# DC_STEP_DRIVER.net
KiCad netlist of a schematic drawn in EAGLE
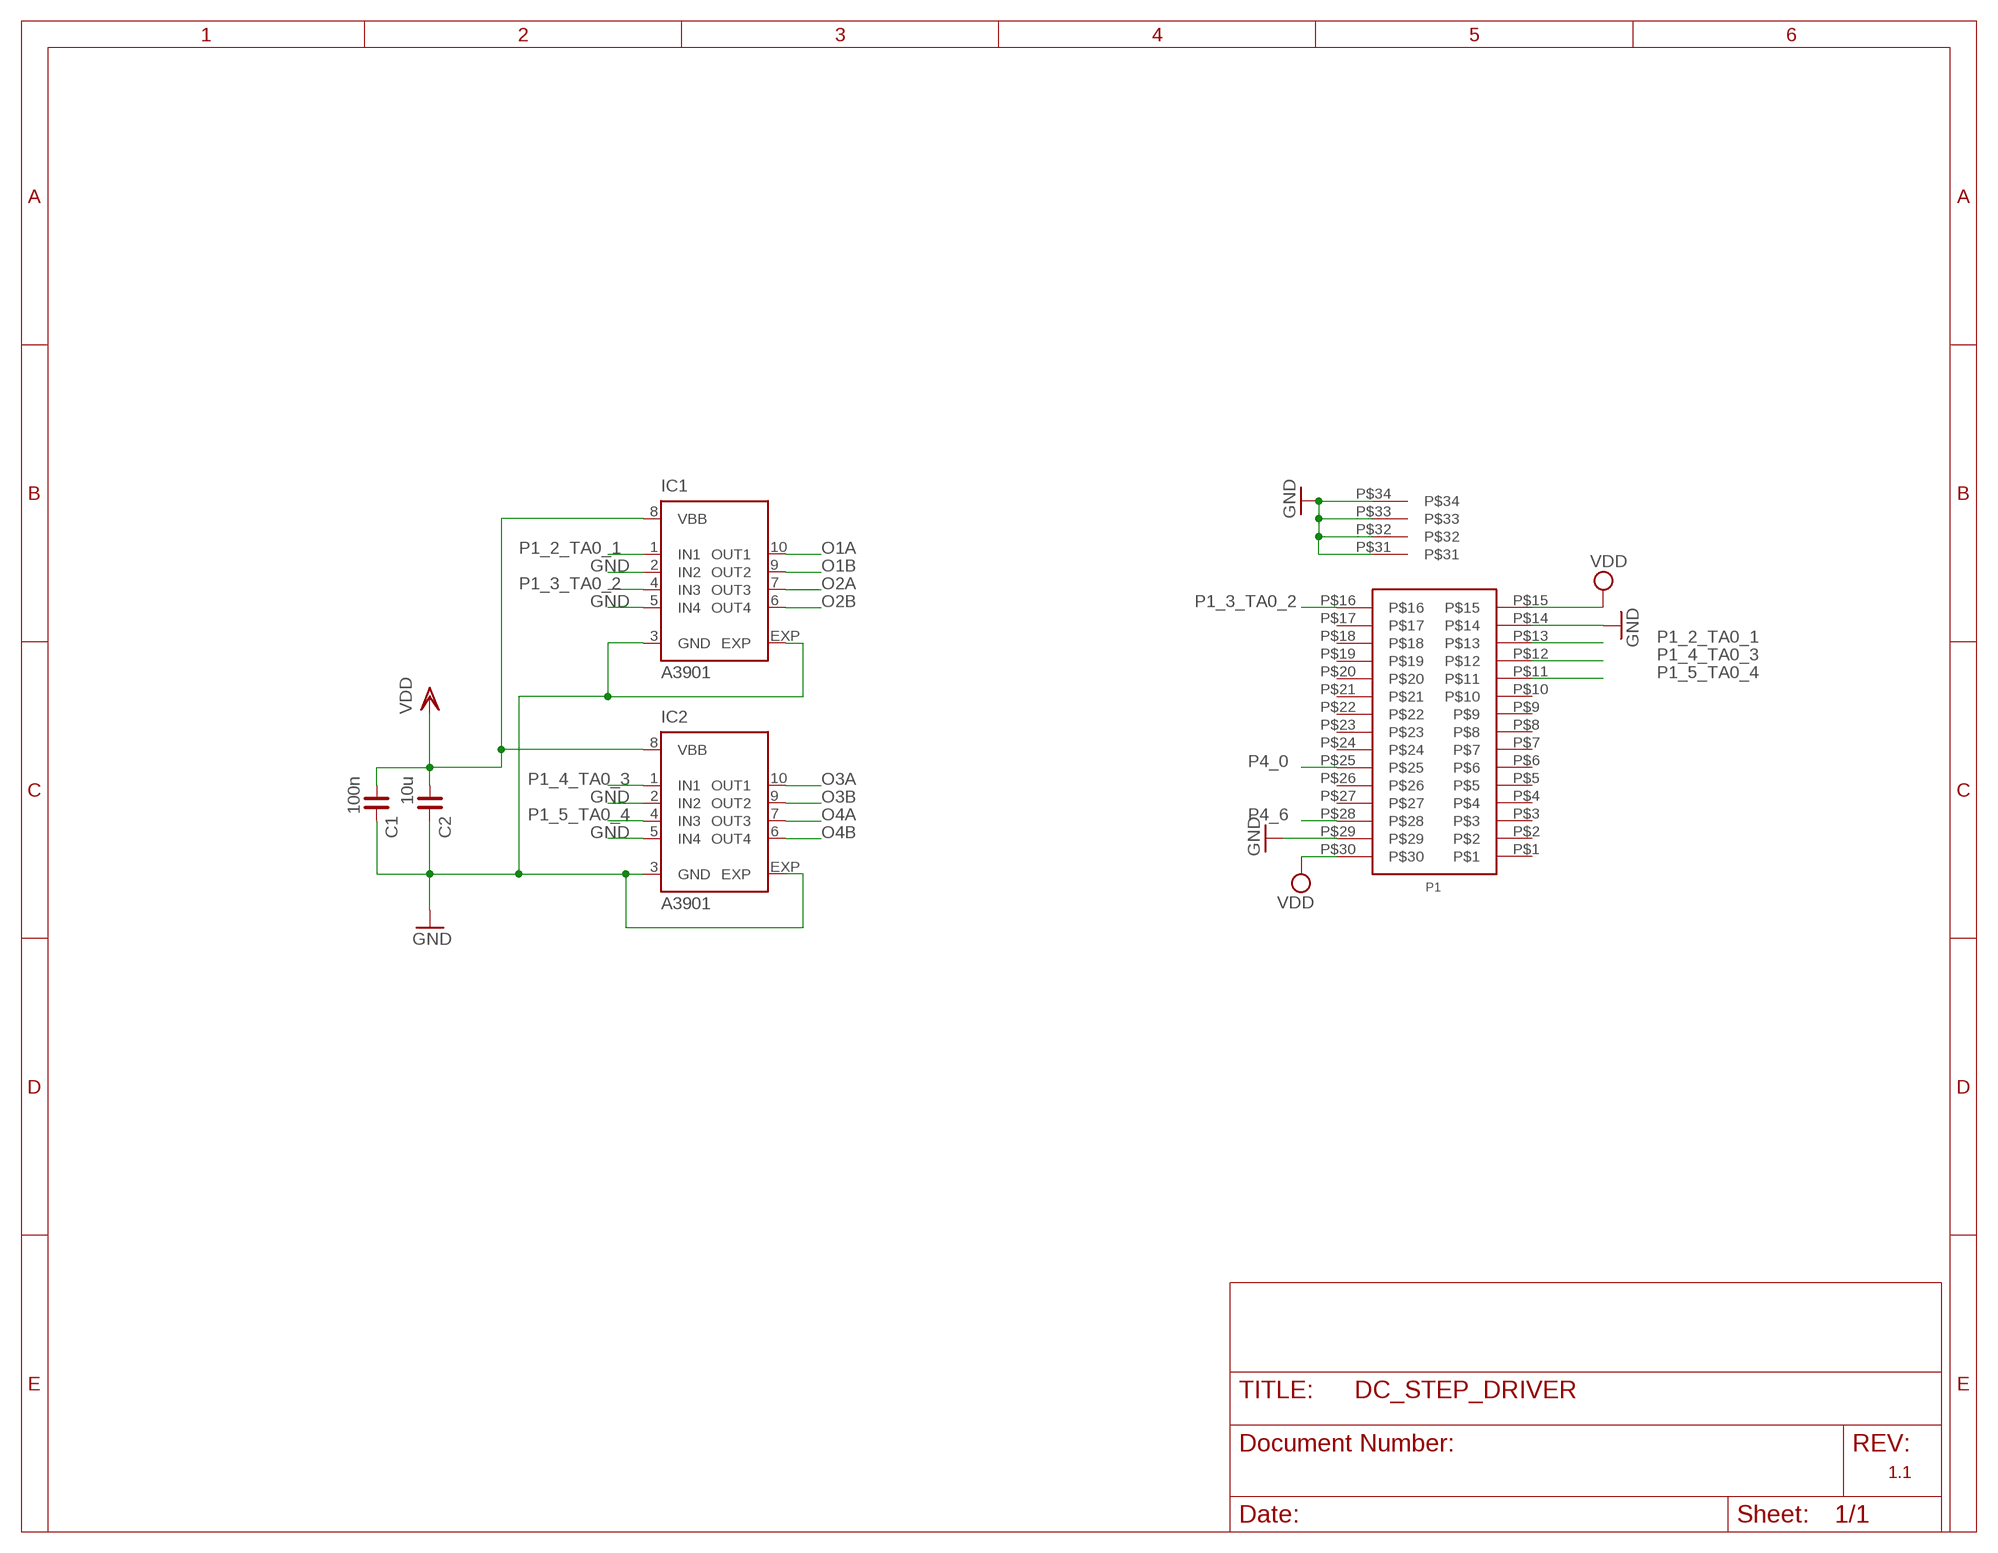
[diagram p0: schematic, sheet 1]

(export (version "E")
  (design (tool "Eeschema 10.0.6"))
  (components
    (comp (ref "C1")
      (value "100n")
      (footprint "eagle-import:C0402")
      (libsource (lib "eagle-import") (part "C_0402"))
    )
    (comp (ref "C2")
      (value "10u")
      (footprint "eagle-import:C0402")
      (libsource (lib "eagle-import") (part "C_0402"))
    )
    (comp (ref "IC1")
      (value "A3901")
      (footprint "eagle-import:DFN10-3X3")
      (fields (field (name "MPN") "A3901SEJTR-T"))
      (libsource (lib "eagle-import") (part "A3901"))
    )
    (comp (ref "IC2")
      (value "A3901")
      (footprint "eagle-import:DFN10-3X3")
      (fields (field (name "MPN") "A3901SEJTR-T"))
      (libsource (lib "eagle-import") (part "A3901"))
    )
    (comp (ref "P1")
      (value "55909-0374")
      (footprint "eagle-import:55909-0374_PLUG")
      (libsource (lib "eagle-import") (part "55909-0374_PLUG"))
    )
  )
  (nets
    (net (code "1") (name "/O1A") (class "Default")
      (node (ref "IC1") (pin "10") (pinfunction "OUT1_10") (pintype "output"))
    )
    (net (code "2") (name "/O1B") (class "Default")
      (node (ref "IC1") (pin "9") (pinfunction "OUT2_9") (pintype "output"))
    )
    (net (code "3") (name "/O2A") (class "Default")
      (node (ref "IC1") (pin "7") (pinfunction "OUT3_7") (pintype "output"))
    )
    (net (code "4") (name "/O2B") (class "Default")
      (node (ref "IC1") (pin "6") (pinfunction "OUT4_6") (pintype "output"))
    )
    (net (code "5") (name "/O3A") (class "Default")
      (node (ref "IC2") (pin "10") (pinfunction "OUT1_10") (pintype "output"))
    )
    (net (code "6") (name "/O3B") (class "Default")
      (node (ref "IC2") (pin "9") (pinfunction "OUT2_9") (pintype "output"))
    )
    (net (code "7") (name "/O4A") (class "Default")
      (node (ref "IC2") (pin "7") (pinfunction "OUT3_7") (pintype "output"))
    )
    (net (code "8") (name "/O4B") (class "Default")
      (node (ref "IC2") (pin "6") (pinfunction "OUT4_6") (pintype "output"))
    )
    (net (code "9") (name "/P1_2_TA0_1") (class "Default")
      (node (ref "IC1") (pin "1") (pinfunction "IN1_1") (pintype "input"))
      (node (ref "P1") (pin "P$13") (pinfunction "P$13_P$13") (pintype "bidirectional"))
    )
    (net (code "10") (name "/P1_3_TA0_2") (class "Default")
      (node (ref "IC1") (pin "4") (pinfunction "IN3_4") (pintype "input"))
      (node (ref "P1") (pin "P$16") (pinfunction "P$16_P$16") (pintype "bidirectional"))
    )
    (net (code "11") (name "/P1_4_TA0_3") (class "Default")
      (node (ref "IC2") (pin "1") (pinfunction "IN1_1") (pintype "input"))
      (node (ref "P1") (pin "P$12") (pinfunction "P$12_P$12") (pintype "bidirectional"))
    )
    (net (code "12") (name "/P1_5_TA0_4") (class "Default")
      (node (ref "IC2") (pin "4") (pinfunction "IN3_4") (pintype "input"))
      (node (ref "P1") (pin "P$11") (pinfunction "P$11_P$11") (pintype "bidirectional"))
    )
    (net (code "13") (name "/P4_0") (class "Default")
      (node (ref "P1") (pin "P$25") (pinfunction "P$25_P$25") (pintype "bidirectional"))
    )
    (net (code "14") (name "/P4_6") (class "Default")
      (node (ref "P1") (pin "P$28") (pinfunction "P$28_P$28") (pintype "bidirectional"))
    )
    (net (code "15") (name "GND") (class "Default")
      (node (ref "C1") (pin "2") (pinfunction "2_2") (pintype "passive"))
      (node (ref "C2") (pin "2") (pinfunction "2_2") (pintype "passive"))
      (node (ref "IC1") (pin "2") (pinfunction "IN2_2") (pintype "input"))
      (node (ref "IC1") (pin "3") (pinfunction "GND_3") (pintype "power_in"))
      (node (ref "IC1") (pin "5") (pinfunction "IN4_5") (pintype "input"))
      (node (ref "IC1") (pin "EXP") (pinfunction "EXP_EXP") (pintype "passive"))
      (node (ref "IC2") (pin "2") (pinfunction "IN2_2") (pintype "input"))
      (node (ref "IC2") (pin "3") (pinfunction "GND_3") (pintype "power_in"))
      (node (ref "IC2") (pin "5") (pinfunction "IN4_5") (pintype "input"))
      (node (ref "IC2") (pin "EXP") (pinfunction "EXP_EXP") (pintype "passive"))
      (node (ref "P1") (pin "P$14") (pinfunction "P$14_P$14") (pintype "bidirectional"))
      (node (ref "P1") (pin "P$29") (pinfunction "P$29_P$29") (pintype "bidirectional"))
      (node (ref "P1") (pin "P$31") (pinfunction "P$31_P$31") (pintype "bidirectional"))
      (node (ref "P1") (pin "P$32") (pinfunction "P$32_P$32") (pintype "bidirectional"))
      (node (ref "P1") (pin "P$33") (pinfunction "P$33_P$33") (pintype "bidirectional"))
      (node (ref "P1") (pin "P$34") (pinfunction "P$34_P$34") (pintype "bidirectional"))
    )
    (net (code "16") (name "VDD") (class "Default")
      (node (ref "C1") (pin "1") (pinfunction "1_1") (pintype "passive"))
      (node (ref "C2") (pin "1") (pinfunction "1_1") (pintype "passive"))
      (node (ref "IC1") (pin "8") (pinfunction "VBB_8") (pintype "power_in"))
      (node (ref "IC2") (pin "8") (pinfunction "VBB_8") (pintype "power_in"))
      (node (ref "P1") (pin "P$15") (pinfunction "P$15_P$15") (pintype "bidirectional"))
      (node (ref "P1") (pin "P$30") (pinfunction "P$30_P$30") (pintype "bidirectional"))
    )
    (net (code "17") (name "unconnected-(P1-PadP$1)") (class "Default")
      (node (ref "P1") (pin "P$1") (pinfunction "P$1_P$1") (pintype "bidirectional"))
    )
    (net (code "18") (name "unconnected-(P1-PadP$2)") (class "Default")
      (node (ref "P1") (pin "P$2") (pinfunction "P$2_P$2") (pintype "bidirectional"))
    )
    (net (code "19") (name "unconnected-(P1-PadP$3)") (class "Default")
      (node (ref "P1") (pin "P$3") (pinfunction "P$3_P$3") (pintype "bidirectional"))
    )
    (net (code "20") (name "unconnected-(P1-PadP$4)") (class "Default")
      (node (ref "P1") (pin "P$4") (pinfunction "P$4_P$4") (pintype "bidirectional"))
    )
    (net (code "21") (name "unconnected-(P1-PadP$5)") (class "Default")
      (node (ref "P1") (pin "P$5") (pinfunction "P$5_P$5") (pintype "bidirectional"))
    )
    (net (code "22") (name "unconnected-(P1-PadP$6)") (class "Default")
      (node (ref "P1") (pin "P$6") (pinfunction "P$6_P$6") (pintype "bidirectional"))
    )
    (net (code "23") (name "unconnected-(P1-PadP$7)") (class "Default")
      (node (ref "P1") (pin "P$7") (pinfunction "P$7_P$7") (pintype "bidirectional"))
    )
    (net (code "24") (name "unconnected-(P1-PadP$8)") (class "Default")
      (node (ref "P1") (pin "P$8") (pinfunction "P$8_P$8") (pintype "bidirectional"))
    )
    (net (code "25") (name "unconnected-(P1-PadP$9)") (class "Default")
      (node (ref "P1") (pin "P$9") (pinfunction "P$9_P$9") (pintype "bidirectional"))
    )
    (net (code "26") (name "unconnected-(P1-PadP$10)") (class "Default")
      (node (ref "P1") (pin "P$10") (pinfunction "P$10_P$10") (pintype "bidirectional"))
    )
    (net (code "27") (name "unconnected-(P1-PadP$17)") (class "Default")
      (node (ref "P1") (pin "P$17") (pinfunction "P$17_P$17") (pintype "bidirectional"))
    )
    (net (code "28") (name "unconnected-(P1-PadP$18)") (class "Default")
      (node (ref "P1") (pin "P$18") (pinfunction "P$18_P$18") (pintype "bidirectional"))
    )
    (net (code "29") (name "unconnected-(P1-PadP$19)") (class "Default")
      (node (ref "P1") (pin "P$19") (pinfunction "P$19_P$19") (pintype "bidirectional"))
    )
    (net (code "30") (name "unconnected-(P1-PadP$20)") (class "Default")
      (node (ref "P1") (pin "P$20") (pinfunction "P$20_P$20") (pintype "bidirectional"))
    )
    (net (code "31") (name "unconnected-(P1-PadP$21)") (class "Default")
      (node (ref "P1") (pin "P$21") (pinfunction "P$21_P$21") (pintype "bidirectional"))
    )
    (net (code "32") (name "unconnected-(P1-PadP$22)") (class "Default")
      (node (ref "P1") (pin "P$22") (pinfunction "P$22_P$22") (pintype "bidirectional"))
    )
    (net (code "33") (name "unconnected-(P1-PadP$23)") (class "Default")
      (node (ref "P1") (pin "P$23") (pinfunction "P$23_P$23") (pintype "bidirectional"))
    )
    (net (code "34") (name "unconnected-(P1-PadP$24)") (class "Default")
      (node (ref "P1") (pin "P$24") (pinfunction "P$24_P$24") (pintype "bidirectional"))
    )
    (net (code "35") (name "unconnected-(P1-PadP$26)") (class "Default")
      (node (ref "P1") (pin "P$26") (pinfunction "P$26_P$26") (pintype "bidirectional"))
    )
    (net (code "36") (name "unconnected-(P1-PadP$27)") (class "Default")
      (node (ref "P1") (pin "P$27") (pinfunction "P$27_P$27") (pintype "bidirectional"))
    )
  )
)
